# AEM00941_harvesting.net
KiCad netlist of a schematic drawn in Altium Designer
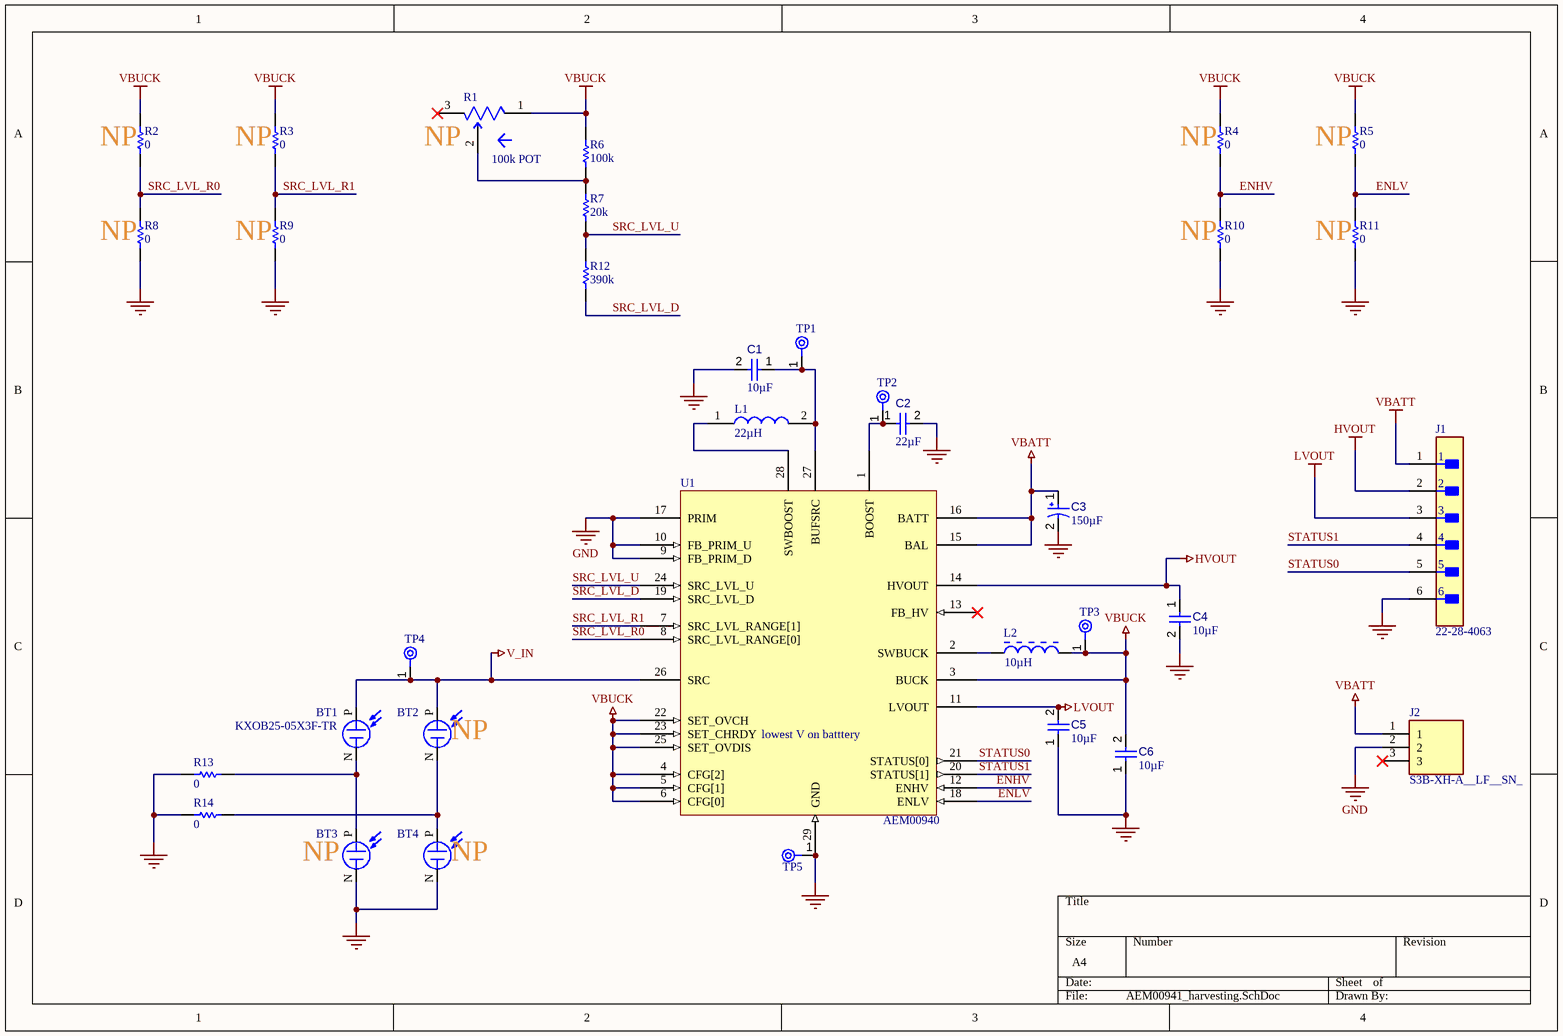
[diagram p0: AEM00941_harvesting.SchDoc]

(export (version "E")
  (design (tool "Eeschema 10.0.6"))
  (components
    (comp (ref "BT1")
      (value "KXOB25-05X3F-TR")
      (footprint "SOLAR_KXOB25-14X1F-TR")
      (description "Monocrystalline Solar Cell 30.7 mW 690 mV")
      (fields (field (name "MF") "ANYSOLAR Ltd") (field (name "MP") "KXOB25-14X1F-TR"))
      (libsource (lib "KXOB25-14X1F-TR") (part "KXOB25-14X1F-TR"))
    )
    (comp (ref "BT2")
      (value "KXOB25-05X3F-TR")
      (footprint "SOLAR_KXOB25-14X1F-TR")
      (description "Monocrystalline Solar Cell 30.7 mW 690 mV")
      (fields (field (name "MF") "ANYSOLAR Ltd") (field (name "MP") "KXOB25-14X1F-TR"))
      (libsource (lib "KXOB25-14X1F-TR") (part "KXOB25-14X1F-TR"))
    )
    (comp (ref "BT3")
      (value "KXOB25-05X3F-TR")
      (footprint "SOLAR_KXOB25-14X1F-TR")
      (description "Monocrystalline Solar Cell 30.7 mW 690 mV")
      (fields (field (name "MF") "ANYSOLAR Ltd") (field (name "MP") "KXOB25-14X1F-TR"))
      (libsource (lib "KXOB25-14X1F-TR") (part "KXOB25-14X1F-TR"))
    )
    (comp (ref "BT4")
      (value "KXOB25-05X3F-TR")
      (footprint "SOLAR_KXOB25-14X1F-TR")
      (description "Monocrystalline Solar Cell 30.7 mW 690 mV")
      (fields (field (name "MF") "ANYSOLAR Ltd") (field (name "MP") "KXOB25-14X1F-TR"))
      (libsource (lib "KXOB25-14X1F-TR") (part "KXOB25-14X1F-TR"))
    )
    (comp (ref "C1")
      (value "10µF")
      (footprint "CAPC0603(1608)100_L")
      (description "Chip Capacitor, 10µF +/-20%, 10V, 0603, Thickness 1 mm")
      (fields (field (name "TOLERANCE") "10%") (field (name "Comment") "Capacitor 10µF +/-20% 10V 0603"))
      (libsource (lib "University of New South Wales") (part "CAP-NP-2"))
    )
    (comp (ref "C2")
      (value "22µF")
      (footprint "CAPC0603(1608)100_L")
      (description "Chip Capacitor, 10µF +/-20%, 10V, 0603, Thickness 1 mm")
      (fields (field (name "TOLERANCE") "10%") (field (name "Comment") "Capacitor 10µF +/-20% 10V 0603"))
      (libsource (lib "University of New South Wales") (part "CAP-NP-2"))
    )
    (comp (ref "C3")
      (value "150µF")
      (footprint "AVX-TAJ-B-2_L")
      (description "Standard Tantalum, 10 uF, +/- 10%, 16 V, -55 to 125 degC, 1210 (3528 Metric), RoHS, Tape and Reel")
      (fields (field (name "MANUFACTURER") "AVX") (field (name "TOLERANCE") "10%"))
      (libsource (lib "Aryan Agarwal") (part "CAP-P-2"))
    )
    (comp (ref "C4")
      (value "10µF")
      (footprint "CAPC0603(1608)100_L")
      (description "Chip Capacitor, 10µF +/-20%, 10V, 0603, Thickness 1 mm")
      (fields (field (name "TOLERANCE") "10%") (field (name "Comment") "Capacitor 10µF +/-20% 10V 0603"))
      (libsource (lib "University of New South Wales") (part "CAP-NP-2"))
    )
    (comp (ref "C5")
      (value "10µF")
      (footprint "CAPC0603(1608)100_L")
      (description "Chip Capacitor, 10µF +/-20%, 10V, 0603, Thickness 1 mm")
      (fields (field (name "TOLERANCE") "10%") (field (name "Comment") "Capacitor 10µF +/-20% 10V 0603"))
      (libsource (lib "University of New South Wales") (part "CAP-NP-2"))
    )
    (comp (ref "C6")
      (value "10µF")
      (footprint "CAPC0603(1608)100_L")
      (description "Chip Capacitor, 10µF +/-20%, 10V, 0603, Thickness 1 mm")
      (fields (field (name "TOLERANCE") "10%") (field (name "Comment") "Capacitor 10µF +/-20% 10V 0603"))
      (libsource (lib "University of New South Wales") (part "CAP-NP-2"))
    )
    (comp (ref "J1")
      (value "22-28-4063")
      (footprint "FP-22-28-4063-MFG")
      (description "CONN HEADER VERT 6POS 2.54MM")
      (libsource (lib "Altium Content Vault") (part "f2cb566baf1c37ab5a3b8e90bbeafd6"))
    )
    (comp (ref "J2")
      (value "S3B-XH-A__LF__SN_")
      (footprint "SamacSys:SHDRRA3W64P0X250_1X3_990X1150X610P")
      (description "Connector")
      (fields (field (name "MANUFACTURER_PART_NUMBER") "S3B-XH-A (LF)(SN)"))
      (libsource (lib "*") (part "S3B-XH-A__LF__SN_"))
    )
    (comp (ref "L1")
      (value "22µH")
      (footprint "SamacSys:LPS4018223MRC")
      (description "Inductor")
      (fields
        (field (name "MANUFACTURER_PART_NUMBER") "LPS4018-223MRC")
        (field (name "MOUSER PART NUMBER") "994-LPS4018-223MRC")
      )
      (libsource (lib "*") (part "LPS4018-223MRC"))
    )
    (comp (ref "L2")
      (value "10µH")
      (footprint "MURA-BLM18-F-H1-CHIP-2_V")
      (fields (field (name "TOLERANCE") "25%") (field (name "MANUFACTURER") "Murata"))
      (libsource (lib "University of New South Wales") (part "IND-FB-2"))
    )
    (comp (ref "R1")
      (value "100k POT")
      (footprint "FP-PV36W-MFG")
      (description "TRIMMER 1K OHM 0.5W PC PIN TOP")
      (fields
        (field (name "OCTOPART") "https://octopart.com/pv36w102c01b00-bourns-71612321")
        (field (name "MANUFACTURER PART NUMBER") "PV36W102C01B00")
      )
      (libsource (lib "Altium Content Vault") (part "3b5a993e1b8b55ba5d1e0805a406c64"))
    )
    (comp (ref "R2")
      (value "0")
      (footprint "RESC1005X40X25ML05T10")
      (description "Chip Resistor, 0 Ohm, 0.063 W, -55 to 155 degC, 0402 (1005 Metric)")
      (fields (field (name "POWER") "63mW") (field (name "Comment") "Resistor 0R 0402 63 mW"))
      (libsource (lib "University of New South Wales") (part "RES-2"))
    )
    (comp (ref "R3")
      (value "0")
      (footprint "RESC1005X40X25ML05T10")
      (description "Chip Resistor, 0 Ohm, 0.063 W, -55 to 155 degC, 0402 (1005 Metric)")
      (fields (field (name "POWER") "63mW") (field (name "Comment") "Resistor 0R 0402 63 mW"))
      (libsource (lib "University of New South Wales") (part "RES-2"))
    )
    (comp (ref "R4")
      (value "0")
      (footprint "RESC1005X40X25ML05T10")
      (description "Chip Resistor, 0 Ohm, 0.063 W, -55 to 155 degC, 0402 (1005 Metric)")
      (fields (field (name "POWER") "63mW") (field (name "Comment") "Resistor 0R 0402 63 mW"))
      (libsource (lib "University of New South Wales") (part "RES-2"))
    )
    (comp (ref "R5")
      (value "0")
      (footprint "RESC1005X40X25ML05T10")
      (description "Chip Resistor, 0 Ohm, 0.063 W, -55 to 155 degC, 0402 (1005 Metric)")
      (fields (field (name "POWER") "63mW") (field (name "Comment") "Resistor 0R 0402 63 mW"))
      (libsource (lib "University of New South Wales") (part "RES-2"))
    )
    (comp (ref "R6")
      (value "100k")
      (footprint "RESC1608X55X25ML10T15")
      (description "Chip Resistor, 0 Ohm, 0.1 W, -55 to 155 degC, 0603 (1608 Metric)")
      (fields (field (name "POWER") "100mW") (field (name "TOLERANCE") "5%"))
      (libsource (lib "University of New South Wales") (part "RES-2"))
    )
    (comp (ref "R7")
      (value "20k")
      (footprint "RESC1608X55X25ML10T15")
      (description "Chip Resistor, 0 Ohm, 0.1 W, -55 to 155 degC, 0603 (1608 Metric)")
      (fields (field (name "POWER") "100mW") (field (name "TOLERANCE") "5%"))
      (libsource (lib "University of New South Wales") (part "RES-2"))
    )
    (comp (ref "R8")
      (value "0")
      (footprint "RESC1005X40X25ML05T10")
      (description "Chip Resistor, 0 Ohm, 0.063 W, -55 to 155 degC, 0402 (1005 Metric)")
      (fields (field (name "POWER") "63mW") (field (name "Comment") "Resistor 0R 0402 63 mW"))
      (libsource (lib "University of New South Wales") (part "RES-2"))
    )
    (comp (ref "R9")
      (value "0")
      (footprint "RESC1005X40X25ML05T10")
      (description "Chip Resistor, 0 Ohm, 0.063 W, -55 to 155 degC, 0402 (1005 Metric)")
      (fields (field (name "POWER") "63mW") (field (name "Comment") "Resistor 0R 0402 63 mW"))
      (libsource (lib "University of New South Wales") (part "RES-2"))
    )
    (comp (ref "R10")
      (value "0")
      (footprint "RESC1005X40X25ML05T10")
      (description "Chip Resistor, 0 Ohm, 0.063 W, -55 to 155 degC, 0402 (1005 Metric)")
      (fields (field (name "POWER") "63mW") (field (name "Comment") "Resistor 0R 0402 63 mW"))
      (libsource (lib "University of New South Wales") (part "RES-2"))
    )
    (comp (ref "R11")
      (value "0")
      (footprint "RESC1005X40X25ML05T10")
      (description "Chip Resistor, 0 Ohm, 0.063 W, -55 to 155 degC, 0402 (1005 Metric)")
      (fields (field (name "POWER") "63mW") (field (name "Comment") "Resistor 0R 0402 63 mW"))
      (libsource (lib "University of New South Wales") (part "RES-2"))
    )
    (comp (ref "R12")
      (value "390k")
      (footprint "RESC1608X55X25ML10T15")
      (description "Chip Resistor, 0 Ohm, 0.1 W, -55 to 155 degC, 0603 (1608 Metric)")
      (fields (field (name "POWER") "100mW") (field (name "TOLERANCE") "5%"))
      (libsource (lib "University of New South Wales") (part "RES-2"))
    )
    (comp (ref "R13")
      (value "0")
      (footprint "RESC1005X40X25ML05T10")
      (description "Chip Resistor, 0 Ohm, 0.063 W, -55 to 155 degC, 0402 (1005 Metric)")
      (fields (field (name "POWER") "63mW") (field (name "Comment") "Resistor 0R 0402 63 mW"))
      (libsource (lib "University of New South Wales") (part "RES-2"))
    )
    (comp (ref "R14")
      (value "0")
      (footprint "RESC1005X40X25ML05T10")
      (description "Chip Resistor, 0 Ohm, 0.063 W, -55 to 155 degC, 0402 (1005 Metric)")
      (fields (field (name "POWER") "63mW") (field (name "Comment") "Resistor 0R 0402 63 mW"))
      (libsource (lib "University of New South Wales") (part "RES-2"))
    )
    (comp (ref "TP1")
      (value "TPAD6R")
      (footprint "TP06R")
      (description "0.6mm round")
      (libsource (lib "Aryan Agarwal") (part "CMP-001-0001-4"))
    )
    (comp (ref "TP2")
      (value "TPAD6R")
      (footprint "TP06R")
      (description "0.6mm round")
      (libsource (lib "Aryan Agarwal") (part "CMP-001-0001-4"))
    )
    (comp (ref "TP3")
      (value "TPAD6R")
      (footprint "TP06R")
      (description "0.6mm round")
      (libsource (lib "Aryan Agarwal") (part "CMP-001-0001-4"))
    )
    (comp (ref "TP4")
      (value "TPAD6R")
      (footprint "TP06R")
      (description "0.6mm round")
      (libsource (lib "Aryan Agarwal") (part "CMP-001-0001-4"))
    )
    (comp (ref "TP5")
      (value "TPAD6R")
      (footprint "TP06R")
      (description "0.6mm round")
      (libsource (lib "Aryan Agarwal") (part "CMP-001-0001-4"))
    )
    (comp (ref "U1")
      (value "AEM00940")
      (footprint "QFN40P400X400X85_HS-29N")
      (libsource (lib "Schlib3") (part "AEM00941"))
    )
  )
  (nets
    (net (code "1") (name "/ENHV") (class "Default")
      (node (ref "R10") (pin "2") (pinfunction "2_2") (pintype "passive"))
      (node (ref "R4") (pin "1") (pinfunction "1_1") (pintype "passive"))
      (node (ref "U1") (pin "12") (pinfunction "ENHV_12") (pintype "input"))
    )
    (net (code "2") (name "/ENLV") (class "Default")
      (node (ref "R11") (pin "2") (pinfunction "2_2") (pintype "passive"))
      (node (ref "R5") (pin "1") (pinfunction "1_1") (pintype "passive"))
      (node (ref "U1") (pin "18") (pinfunction "ENLV_18") (pintype "input"))
    )
    (net (code "3") (name "/SRC_LVL_D") (class "Default")
      (node (ref "R12") (pin "1") (pinfunction "1_1") (pintype "passive"))
      (node (ref "U1") (pin "19") (pinfunction "SRC_LVL_D_19") (pintype "input"))
    )
    (net (code "4") (name "/SRC_LVL_R0") (class "Default")
      (node (ref "R2") (pin "1") (pinfunction "1_1") (pintype "passive"))
      (node (ref "R8") (pin "2") (pinfunction "2_2") (pintype "passive"))
      (node (ref "U1") (pin "8") (pinfunction "SRC_LVL_RANGE[0]_8") (pintype "input"))
    )
    (net (code "5") (name "/SRC_LVL_R1") (class "Default")
      (node (ref "R3") (pin "1") (pinfunction "1_1") (pintype "passive"))
      (node (ref "R9") (pin "2") (pinfunction "2_2") (pintype "passive"))
      (node (ref "U1") (pin "7") (pinfunction "SRC_LVL_RANGE[1]_7") (pintype "input"))
    )
    (net (code "6") (name "/SRC_LVL_U") (class "Default")
      (node (ref "R12") (pin "2") (pinfunction "2_2") (pintype "passive"))
      (node (ref "R7") (pin "1") (pinfunction "1_1") (pintype "passive"))
      (node (ref "U1") (pin "24") (pinfunction "SRC_LVL_U_24") (pintype "input"))
    )
    (net (code "7") (name "/STATUS0") (class "Default")
      (node (ref "J1") (pin "5") (pinfunction "5_5") (pintype "passive"))
      (node (ref "U1") (pin "21") (pinfunction "STATUS[0]_21") (pintype "output"))
    )
    (net (code "8") (name "/STATUS1") (class "Default")
      (node (ref "J1") (pin "4") (pinfunction "4_4") (pintype "passive"))
      (node (ref "U1") (pin "20") (pinfunction "STATUS[1]_20") (pintype "output"))
    )
    (net (code "9") (name "GND") (class "Default")
      (node (ref "BT3") (pin "N") (pinfunction "N_N") (pintype "passive"))
      (node (ref "BT4") (pin "N") (pinfunction "N_N") (pintype "passive"))
      (node (ref "C1") (pin "2") (pinfunction "2_2") (pintype "passive"))
      (node (ref "C2") (pin "2") (pinfunction "2_2") (pintype "passive"))
      (node (ref "C3") (pin "2") (pinfunction "2_2") (pintype "passive"))
      (node (ref "C4") (pin "2") (pinfunction "2_2") (pintype "passive"))
      (node (ref "C5") (pin "1") (pinfunction "1_1") (pintype "passive"))
      (node (ref "C6") (pin "1") (pinfunction "1_1") (pintype "passive"))
      (node (ref "J1") (pin "6") (pinfunction "6_6") (pintype "passive"))
      (node (ref "J2") (pin "2") (pinfunction "2_2") (pintype "passive"))
      (node (ref "R10") (pin "1") (pinfunction "1_1") (pintype "passive"))
      (node (ref "R11") (pin "1") (pinfunction "1_1") (pintype "passive"))
      (node (ref "R13") (pin "2") (pinfunction "2_2") (pintype "passive"))
      (node (ref "R14") (pin "2") (pinfunction "2_2") (pintype "passive"))
      (node (ref "R8") (pin "1") (pinfunction "1_1") (pintype "passive"))
      (node (ref "R9") (pin "1") (pinfunction "1_1") (pintype "passive"))
      (node (ref "TP5") (pin "1") (pinfunction "TP_1") (pintype "passive"))
      (node (ref "U1") (pin "10") (pinfunction "FB_PRIM_U_10") (pintype "input"))
      (node (ref "U1") (pin "17") (pinfunction "PRIM_17") (pintype "power_in"))
      (node (ref "U1") (pin "29") (pinfunction "GND_29") (pintype "input"))
      (node (ref "U1") (pin "9") (pinfunction "FB_PRIM_D_9") (pintype "input"))
    )
    (net (code "10") (name "HVOUT") (class "Default")
      (node (ref "C4") (pin "1") (pinfunction "1_1") (pintype "passive"))
      (node (ref "J1") (pin "2") (pinfunction "2_2") (pintype "passive"))
      (node (ref "U1") (pin "14") (pinfunction "HVOUT_14") (pintype "power_in"))
    )
    (net (code "11") (name "LVOUT") (class "Default")
      (node (ref "C5") (pin "2") (pinfunction "2_2") (pintype "passive"))
      (node (ref "J1") (pin "3") (pinfunction "3_3") (pintype "passive"))
      (node (ref "U1") (pin "11") (pinfunction "LVOUT_11") (pintype "power_in"))
    )
    (net (code "12") (name "Net-(BT1-PadN)") (class "Default")
      (node (ref "BT1") (pin "N") (pinfunction "N_N") (pintype "passive"))
      (node (ref "BT3") (pin "P") (pinfunction "P_P") (pintype "passive"))
      (node (ref "R13") (pin "1") (pinfunction "1_1") (pintype "passive"))
    )
    (net (code "13") (name "Net-(BT2-PadN)") (class "Default")
      (node (ref "BT2") (pin "N") (pinfunction "N_N") (pintype "passive"))
      (node (ref "BT4") (pin "P") (pinfunction "P_P") (pintype "passive"))
      (node (ref "R14") (pin "1") (pinfunction "1_1") (pintype "passive"))
    )
    (net (code "14") (name "Net-(R1-Wiper)") (class "Default")
      (node (ref "R1") (pin "2") (pinfunction "Wiper_2") (pintype "passive"))
      (node (ref "R6") (pin "1") (pinfunction "1_1") (pintype "passive"))
      (node (ref "R7") (pin "2") (pinfunction "2_2") (pintype "passive"))
    )
    (net (code "15") (name "Net-(TP1-TP)") (class "Default")
      (node (ref "C1") (pin "1") (pinfunction "1_1") (pintype "passive"))
      (node (ref "L1") (pin "2") (pinfunction "2_2") (pintype "passive"))
      (node (ref "TP1") (pin "1") (pinfunction "TP_1") (pintype "passive"))
      (node (ref "U1") (pin "27") (pinfunction "BUFSRC_27") (pintype "power_in"))
    )
    (net (code "16") (name "Net-(TP2-TP)") (class "Default")
      (node (ref "C2") (pin "1") (pinfunction "1_1") (pintype "passive"))
      (node (ref "TP2") (pin "1") (pinfunction "TP_1") (pintype "passive"))
      (node (ref "U1") (pin "1") (pinfunction "BOOST_1") (pintype "power_in"))
    )
    (net (code "17") (name "Net-(U1-SWBOOST)") (class "Default")
      (node (ref "L1") (pin "1") (pinfunction "1_1") (pintype "passive"))
      (node (ref "U1") (pin "28") (pinfunction "SWBOOST_28") (pintype "power_in"))
    )
    (net (code "18") (name "Net-(U1-SWBUCK)") (class "Default")
      (node (ref "L2") (pin "1") (pinfunction "1_1") (pintype "passive"))
      (node (ref "U1") (pin "2") (pinfunction "SWBUCK_2") (pintype "power_in"))
    )
    (net (code "19") (name "VBATT") (class "Default")
      (node (ref "C3") (pin "1") (pinfunction "1_1") (pintype "passive"))
      (node (ref "J1") (pin "1") (pinfunction "1_1") (pintype "passive"))
      (node (ref "J2") (pin "1") (pinfunction "1_1") (pintype "passive"))
      (node (ref "U1") (pin "15") (pinfunction "BAL_15") (pintype "power_in"))
      (node (ref "U1") (pin "16") (pinfunction "BATT_16") (pintype "power_in"))
    )
    (net (code "20") (name "VBUCK") (class "Default")
      (node (ref "C6") (pin "2") (pinfunction "2_2") (pintype "passive"))
      (node (ref "L2") (pin "2") (pinfunction "2_2") (pintype "passive"))
      (node (ref "R1") (pin "1") (pinfunction "1_1") (pintype "passive"))
      (node (ref "R2") (pin "2") (pinfunction "2_2") (pintype "passive"))
      (node (ref "R3") (pin "2") (pinfunction "2_2") (pintype "passive"))
      (node (ref "R4") (pin "2") (pinfunction "2_2") (pintype "passive"))
      (node (ref "R5") (pin "2") (pinfunction "2_2") (pintype "passive"))
      (node (ref "R6") (pin "2") (pinfunction "2_2") (pintype "passive"))
      (node (ref "TP3") (pin "1") (pinfunction "TP_1") (pintype "passive"))
      (node (ref "U1") (pin "22") (pinfunction "SET_OVCH_22") (pintype "input"))
      (node (ref "U1") (pin "23") (pinfunction "SET_CHRDY_23") (pintype "input"))
      (node (ref "U1") (pin "25") (pinfunction "SET_OVDIS_25") (pintype "input"))
      (node (ref "U1") (pin "3") (pinfunction "BUCK_3") (pintype "power_in"))
      (node (ref "U1") (pin "4") (pinfunction "CFG[2]_4") (pintype "input"))
      (node (ref "U1") (pin "5") (pinfunction "CFG[1]_5") (pintype "input"))
      (node (ref "U1") (pin "6") (pinfunction "CFG[0]_6") (pintype "input"))
    )
    (net (code "21") (name "V_IN") (class "Default")
      (node (ref "BT1") (pin "P") (pinfunction "P_P") (pintype "passive"))
      (node (ref "BT2") (pin "P") (pinfunction "P_P") (pintype "passive"))
      (node (ref "TP4") (pin "1") (pinfunction "TP_1") (pintype "passive"))
      (node (ref "U1") (pin "26") (pinfunction "SRC_26") (pintype "power_in"))
    )
    (net (code "22") (name "unconnected-(J2-Pad3)") (class "Default")
      (node (ref "J2") (pin "3") (pinfunction "3_3") (pintype "passive+no_connect"))
    )
    (net (code "23") (name "unconnected-(R1-Pad3)") (class "Default")
      (node (ref "R1") (pin "3") (pinfunction "3_3") (pintype "passive+no_connect"))
    )
    (net (code "24") (name "unconnected-(U1-FB_HV-Pad13)") (class "Default")
      (node (ref "U1") (pin "13") (pinfunction "FB_HV_13") (pintype "input+no_connect"))
    )
  )
)
